# SoundBlock.net
KiCad netlist of a schematic drawn in Altium Designer
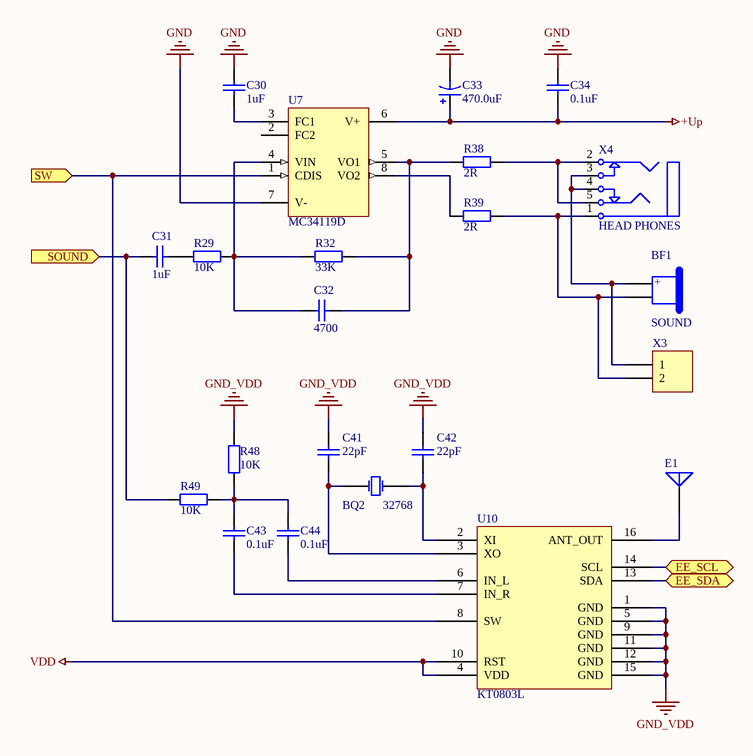
[diagram p0: SoundBlock.SchDoc]

(export (version "E")
  (design (tool "Eeschema 10.0.6"))
  (components
    (comp (ref "BF1")
      (value "SOUND")
      (footprint "HCM12A")
      (description "Magnetic Transducer Buzzer")
      (fields (field (name "PUBLISHER") "Altium Limited"))
      (libsource (lib "Quasar ARM") (part "Elrctro-Magnetic Sound Generator"))
    )
    (comp (ref "BQ2")
      (value "32768")
      (footprint "HC-49/U3H (low profile)")
      (description "Crystal Oscillator")
      (fields (field (name "PUBLISHER") "Altium Limited"))
      (libsource (lib "Quasar ARM") (part "XTAL"))
    )
    (comp (ref "C30")
      (value "1uF")
      (footprint "1206_SMD_Capacitor")
      (description "Capacitor")
      (fields (field (name "PUBLISHER") "Altium Limited"))
      (libsource (lib "Quasar ARM") (part "Capacitor SMD"))
    )
    (comp (ref "C31")
      (value "1uF")
      (footprint "1206_SMD_Capacitor")
      (description "Capacitor")
      (fields (field (name "PUBLISHER") "Altium Limited"))
      (libsource (lib "Quasar ARM") (part "Capacitor SMD"))
    )
    (comp (ref "C32")
      (value "4700")
      (footprint "1206_SMD_Capacitor")
      (description "Capacitor")
      (fields (field (name "PUBLISHER") "Altium Limited"))
      (libsource (lib "Quasar ARM") (part "Capacitor SMD"))
    )
    (comp (ref "C33")
      (value "470.0uF")
      (footprint "E")
      (description "Polarized Capacitor (Radial)")
      (fields (field (name "PUBLISHER") "Altium Limited"))
      (libsource (lib "Quasar ARM") (part "Cap Pol1"))
    )
    (comp (ref "C34")
      (value "0.1uF")
      (footprint "1206_SMD_Capacitor")
      (description "Capacitor")
      (fields (field (name "PUBLISHER") "Altium Limited"))
      (libsource (lib "Quasar ARM") (part "Capacitor SMD"))
    )
    (comp (ref "C41")
      (value "22pF")
      (footprint "0805")
      (description "Capacitor")
      (fields (field (name "PUBLISHER") "Altium Limited"))
      (libsource (lib "Quasar ARM") (part "Capacitor SMD"))
    )
    (comp (ref "C42")
      (value "22pF")
      (footprint "0805")
      (description "Capacitor")
      (fields (field (name "PUBLISHER") "Altium Limited"))
      (libsource (lib "Quasar ARM") (part "Capacitor SMD"))
    )
    (comp (ref "C43")
      (value "0.1uF")
      (footprint "0805")
      (description "Capacitor")
      (fields (field (name "PUBLISHER") "Altium Limited"))
      (libsource (lib "Quasar ARM") (part "Capacitor SMD"))
    )
    (comp (ref "C44")
      (value "0.1uF")
      (footprint "0805")
      (description "Capacitor")
      (fields (field (name "PUBLISHER") "Altium Limited"))
      (libsource (lib "Quasar ARM") (part "Capacitor SMD"))
    )
    (comp (ref "E1")
      (value "Antenna")
      (footprint "PIN1")
      (description "Generic Antenna")
      (fields (field (name "PUBLISHER") "Altium Limited"))
      (libsource (lib "Miscellaneous Devices") (part "Antenna"))
    )
    (comp (ref "R29")
      (value "10K")
      (footprint "1206_SMD_Resistor")
      (description "Resistor")
      (fields (field (name "PUBLISHER") "Altium Limited"))
      (libsource (lib "Quasar ARM") (part "Resistor"))
    )
    (comp (ref "R32")
      (value "33K")
      (footprint "1206_SMD_Resistor")
      (description "Resistor")
      (fields (field (name "PUBLISHER") "Altium Limited"))
      (libsource (lib "Quasar ARM") (part "Resistor"))
    )
    (comp (ref "R38")
      (value "2R")
      (footprint "1206_SMD_Resistor")
      (description "Resistor")
      (fields (field (name "PUBLISHER") "Altium Limited"))
      (libsource (lib "Quasar ARM") (part "Resistor"))
    )
    (comp (ref "R39")
      (value "2R")
      (footprint "1206_SMD_Resistor")
      (description "Resistor")
      (fields (field (name "PUBLISHER") "Altium Limited"))
      (libsource (lib "Quasar ARM") (part "Resistor"))
    )
    (comp (ref "R48")
      (value "10K")
      (footprint "1206_SMD_Resistor")
      (description "Resistor")
      (fields (field (name "PUBLISHER") "Dmitry Kuzmin"))
      (libsource (lib "") (part "Resistor_1"))
    )
    (comp (ref "R49")
      (value "10K")
      (footprint "1206_SMD_Resistor")
      (description "Resistor")
      (fields (field (name "PUBLISHER") "Dmitry Kuzmin"))
      (libsource (lib "Quasar ARM") (part "Resistor"))
    )
    (comp (ref "U7")
      (value "MC34119D")
      (footprint "SO-8")
      (description "Low-Power Audio Amplifier")
      (fields (field (name "PUBLISHER") "Altium Limited"))
      (libsource (lib "Quasar ARM") (part "MC34119D"))
    )
    (comp (ref "U10")
      (value "KT0803L")
      (footprint "SOIC16N_M")
      (libsource (lib "Quasar ARM") (part "KT0803L"))
    )
    (comp (ref "X3")
      (value "SOUND")
      (footprint "HDR1X2")
      (description "Header, 2-Pin")
      (fields (field (name "PUBLISHER") "Altium Limited"))
      (libsource (lib "Quasar ARM") (part "Header 2"))
    )
    (comp (ref "X4")
      (value "HEAD PHONES")
      (footprint "Audio from Aliexpress")
      (description "3-Conductor Jack with 2 break contacts (normals) and 2 auxiliary make contacts")
      (fields (field (name "PUBLISHER") "Altium Limited"))
      (libsource (lib "Quasar ARM") (part "Phonejack Stereo SW"))
    )
  )
  (nets
    (net (code "1") (name "+Up") (class "Default")
      (node (ref "C33") (pin "1") (pinfunction "1_1") (pintype "passive"))
      (node (ref "C34") (pin "1") (pinfunction "1_1") (pintype "passive"))
      (node (ref "U7") (pin "6") (pinfunction "V+_6") (pintype "power_in"))
    )
    (net (code "2") (name "/EE_SCL") (class "Default")
      (node (ref "U10") (pin "14") (pinfunction "SCL_14") (pintype "passive"))
    )
    (net (code "3") (name "/EE_SDA") (class "Default")
      (node (ref "U10") (pin "13") (pinfunction "SDA_13") (pintype "passive"))
    )
    (net (code "4") (name "/SOUND") (class "Default")
      (node (ref "C31") (pin "1") (pinfunction "1_1") (pintype "passive"))
      (node (ref "R49") (pin "1") (pinfunction "1_1") (pintype "passive"))
    )
    (net (code "5") (name "/SW") (class "Default")
      (node (ref "U10") (pin "8") (pinfunction "SW_8") (pintype "passive"))
      (node (ref "U7") (pin "1") (pinfunction "CDIS_1") (pintype "input"))
    )
    (net (code "6") (name "GND") (class "Default")
      (node (ref "C30") (pin "1") (pinfunction "1_1") (pintype "passive"))
      (node (ref "C33") (pin "2") (pinfunction "2_2") (pintype "passive"))
      (node (ref "C34") (pin "2") (pinfunction "2_2") (pintype "passive"))
      (node (ref "U7") (pin "7") (pinfunction "V-_7") (pintype "power_in"))
    )
    (net (code "7") (name "GND_VDD") (class "Default")
      (node (ref "C41") (pin "2") (pinfunction "2_2") (pintype "passive"))
      (node (ref "C42") (pin "2") (pinfunction "2_2") (pintype "passive"))
      (node (ref "R48") (pin "2") (pinfunction "2_2") (pintype "passive"))
      (node (ref "U10") (pin "1") (pinfunction "GND_1") (pintype "passive"))
      (node (ref "U10") (pin "11") (pinfunction "GND_11") (pintype "passive"))
      (node (ref "U10") (pin "12") (pinfunction "GND_12") (pintype "passive"))
      (node (ref "U10") (pin "15") (pinfunction "GND_15") (pintype "passive"))
      (node (ref "U10") (pin "5") (pinfunction "GND_5") (pintype "passive"))
      (node (ref "U10") (pin "9") (pinfunction "GND_9") (pintype "passive"))
    )
    (net (code "8") (name "Net-(BF1-Pad1)") (class "Default")
      (node (ref "BF1") (pin "1") (pinfunction "1_1") (pintype "passive"))
      (node (ref "X3") (pin "1") (pinfunction "1_1") (pintype "passive"))
      (node (ref "X4") (pin "3") (pinfunction "3_3") (pintype "passive"))
      (node (ref "X4") (pin "4") (pinfunction "4_4") (pintype "passive"))
    )
    (net (code "9") (name "Net-(BF1-Pad2)") (class "Default")
      (node (ref "BF1") (pin "2") (pinfunction "2_2") (pintype "passive"))
      (node (ref "R39") (pin "2") (pinfunction "2_2") (pintype "passive"))
      (node (ref "X3") (pin "2") (pinfunction "2_2") (pintype "passive"))
      (node (ref "X4") (pin "1") (pinfunction "1_1") (pintype "passive"))
    )
    (net (code "10") (name "Net-(BQ2-OSC1)") (class "Default")
      (node (ref "BQ2") (pin "1") (pinfunction "OSC1_1") (pintype "passive"))
      (node (ref "C42") (pin "1") (pinfunction "1_1") (pintype "passive"))
      (node (ref "U10") (pin "2") (pinfunction "XI_2") (pintype "passive"))
    )
    (net (code "11") (name "Net-(BQ2-OSC2)") (class "Default")
      (node (ref "BQ2") (pin "2") (pinfunction "OSC2_2") (pintype "passive"))
      (node (ref "C41") (pin "1") (pinfunction "1_1") (pintype "passive"))
      (node (ref "U10") (pin "3") (pinfunction "XO_3") (pintype "passive"))
    )
    (net (code "12") (name "Net-(C31-Pad2)") (class "Default")
      (node (ref "C31") (pin "2") (pinfunction "2_2") (pintype "passive"))
      (node (ref "R29") (pin "1") (pinfunction "1_1") (pintype "passive"))
    )
    (net (code "13") (name "Net-(C43-Pad2)") (class "Default")
      (node (ref "C43") (pin "2") (pinfunction "2_2") (pintype "passive"))
      (node (ref "C44") (pin "2") (pinfunction "2_2") (pintype "passive"))
      (node (ref "R48") (pin "1") (pinfunction "1_1") (pintype "passive"))
      (node (ref "R49") (pin "2") (pinfunction "2_2") (pintype "passive"))
    )
    (net (code "14") (name "Net-(E1-A)") (class "Default")
      (node (ref "E1") (pin "1") (pinfunction "A_1") (pintype "passive"))
      (node (ref "U10") (pin "16") (pinfunction "ANT_OUT_16") (pintype "passive"))
    )
    (net (code "15") (name "Net-(R38-Pad2)") (class "Default")
      (node (ref "R38") (pin "2") (pinfunction "2_2") (pintype "passive"))
      (node (ref "X4") (pin "2") (pinfunction "2_2") (pintype "passive"))
      (node (ref "X4") (pin "5") (pinfunction "5_5") (pintype "passive"))
    )
    (net (code "16") (name "Net-(U7-FC1)") (class "Default")
      (node (ref "C30") (pin "2") (pinfunction "2_2") (pintype "passive"))
      (node (ref "U7") (pin "3") (pinfunction "FC1_3") (pintype "passive"))
    )
    (net (code "17") (name "Net-(U7-VIN)") (class "Default")
      (node (ref "C32") (pin "1") (pinfunction "1_1") (pintype "passive"))
      (node (ref "R29") (pin "2") (pinfunction "2_2") (pintype "passive"))
      (node (ref "R32") (pin "1") (pinfunction "1_1") (pintype "passive"))
      (node (ref "U7") (pin "4") (pinfunction "VIN_4") (pintype "input"))
    )
    (net (code "18") (name "Net-(U7-VO1)") (class "Default")
      (node (ref "C32") (pin "2") (pinfunction "2_2") (pintype "passive"))
      (node (ref "R32") (pin "2") (pinfunction "2_2") (pintype "passive"))
      (node (ref "R38") (pin "1") (pinfunction "1_1") (pintype "passive"))
      (node (ref "U7") (pin "5") (pinfunction "VO1_5") (pintype "output"))
    )
    (net (code "19") (name "Net-(U7-VO2)") (class "Default")
      (node (ref "R39") (pin "1") (pinfunction "1_1") (pintype "passive"))
      (node (ref "U7") (pin "8") (pinfunction "VO2_8") (pintype "output"))
    )
    (net (code "20") (name "Net-(U10-IN_L)") (class "Default")
      (node (ref "C44") (pin "1") (pinfunction "1_1") (pintype "passive"))
      (node (ref "U10") (pin "6") (pinfunction "IN_L_6") (pintype "passive"))
    )
    (net (code "21") (name "Net-(U10-IN_R)") (class "Default")
      (node (ref "C43") (pin "1") (pinfunction "1_1") (pintype "passive"))
      (node (ref "U10") (pin "7") (pinfunction "IN_R_7") (pintype "passive"))
    )
    (net (code "22") (name "VDD") (class "Default")
      (node (ref "U10") (pin "10") (pinfunction "RST_10") (pintype "passive"))
      (node (ref "U10") (pin "4") (pinfunction "VDD_4") (pintype "passive"))
    )
    (net (code "23") (name "unconnected-(U7-FC2-Pad2)") (class "Default")
      (node (ref "U7") (pin "2") (pinfunction "FC2_2") (pintype "passive"))
    )
  )
)
